# MCU_1726036.net
KiCad netlist of a schematic drawn in Altium Designer
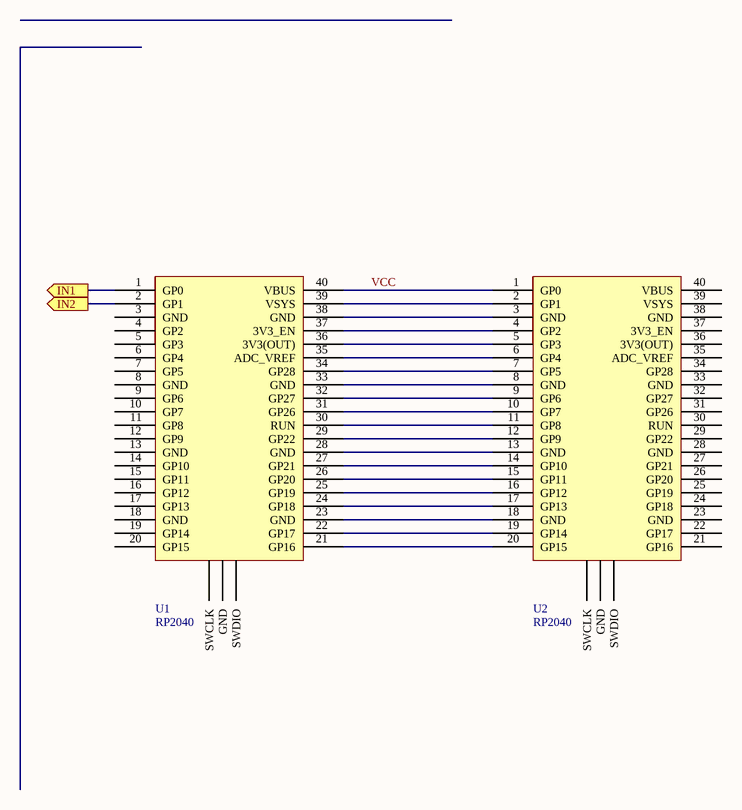
[diagram p0: MCU_1726036.SchDoc]

(export (version "E")
  (design (tool "Eeschema 10.0.6"))
  (components
    (comp (ref "U1") (value "RP2040") (footprint "PICO_MCU") (libsource (lib "PICO_sch") (part "PICO_MCU")))
    (comp (ref "U2") (value "RP2040") (footprint "PICO_MCU") (libsource (lib "PICO_sch") (part "PICO_MCU")))
  )
  (nets
    (net (code "1") (name "/IN1") (class "Default")
      (node (ref "U1") (pin "1") (pinfunction "GP0_1") (pintype "passive"))
    )
    (net (code "2") (name "/IN2") (class "Default")
      (node (ref "U1") (pin "2") (pinfunction "GP1_2") (pintype "passive"))
    )
    (net (code "3") (name "/VCC") (class "Default")
      (node (ref "U1") (pin "40") (pinfunction "VBUS_40") (pintype "passive"))
      (node (ref "U2") (pin "1") (pinfunction "GP0_1") (pintype "passive"))
    )
    (net (code "4") (name "Net-(U1-3V3(OUT))") (class "Default")
      (node (ref "U1") (pin "36") (pinfunction "3V3(OUT)_36") (pintype "passive"))
      (node (ref "U2") (pin "5") (pinfunction "GP3_5") (pintype "passive"))
    )
    (net (code "5") (name "Net-(U1-3V3_EN)") (class "Default")
      (node (ref "U1") (pin "37") (pinfunction "3V3_EN_37") (pintype "passive"))
      (node (ref "U2") (pin "4") (pinfunction "GP2_4") (pintype "passive"))
    )
    (net (code "6") (name "Net-(U1-ADC_VREF)") (class "Default")
      (node (ref "U1") (pin "35") (pinfunction "ADC_VREF_35") (pintype "passive"))
      (node (ref "U2") (pin "6") (pinfunction "GP4_6") (pintype "passive"))
    )
    (net (code "7") (name "Net-(U1-GND-Pad23)") (class "Default")
      (node (ref "U1") (pin "23") (pinfunction "GND_23") (pintype "passive"))
      (node (ref "U2") (pin "18") (pinfunction "GND_18") (pintype "passive"))
    )
    (net (code "8") (name "Net-(U1-GND-Pad28)") (class "Default")
      (node (ref "U1") (pin "28") (pinfunction "GND_28") (pintype "passive"))
      (node (ref "U2") (pin "13") (pinfunction "GND_13") (pintype "passive"))
    )
    (net (code "9") (name "Net-(U1-GND-Pad33)") (class "Default")
      (node (ref "U1") (pin "33") (pinfunction "GND_33") (pintype "passive"))
      (node (ref "U2") (pin "8") (pinfunction "GND_8") (pintype "passive"))
    )
    (net (code "10") (name "Net-(U1-GND-Pad38)") (class "Default")
      (node (ref "U1") (pin "38") (pinfunction "GND_38") (pintype "passive"))
      (node (ref "U2") (pin "3") (pinfunction "GND_3") (pintype "passive"))
    )
    (net (code "11") (name "Net-(U1-GP16)") (class "Default")
      (node (ref "U1") (pin "21") (pinfunction "GP16_21") (pintype "passive"))
      (node (ref "U2") (pin "20") (pinfunction "GP15_20") (pintype "passive"))
    )
    (net (code "12") (name "Net-(U1-GP17)") (class "Default")
      (node (ref "U1") (pin "22") (pinfunction "GP17_22") (pintype "passive"))
      (node (ref "U2") (pin "19") (pinfunction "GP14_19") (pintype "passive"))
    )
    (net (code "13") (name "Net-(U1-GP18)") (class "Default")
      (node (ref "U1") (pin "24") (pinfunction "GP18_24") (pintype "passive"))
      (node (ref "U2") (pin "17") (pinfunction "GP13_17") (pintype "passive"))
    )
    (net (code "14") (name "Net-(U1-GP19)") (class "Default")
      (node (ref "U1") (pin "25") (pinfunction "GP19_25") (pintype "passive"))
      (node (ref "U2") (pin "16") (pinfunction "GP12_16") (pintype "passive"))
    )
    (net (code "15") (name "Net-(U1-GP20)") (class "Default")
      (node (ref "U1") (pin "26") (pinfunction "GP20_26") (pintype "passive"))
      (node (ref "U2") (pin "15") (pinfunction "GP11_15") (pintype "passive"))
    )
    (net (code "16") (name "Net-(U1-GP21)") (class "Default")
      (node (ref "U1") (pin "27") (pinfunction "GP21_27") (pintype "passive"))
      (node (ref "U2") (pin "14") (pinfunction "GP10_14") (pintype "passive"))
    )
    (net (code "17") (name "Net-(U1-GP22)") (class "Default")
      (node (ref "U1") (pin "29") (pinfunction "GP22_29") (pintype "passive"))
      (node (ref "U2") (pin "12") (pinfunction "GP9_12") (pintype "passive"))
    )
    (net (code "18") (name "Net-(U1-GP26)") (class "Default")
      (node (ref "U1") (pin "31") (pinfunction "GP26_31") (pintype "passive"))
      (node (ref "U2") (pin "10") (pinfunction "GP7_10") (pintype "passive"))
    )
    (net (code "19") (name "Net-(U1-GP27)") (class "Default")
      (node (ref "U1") (pin "32") (pinfunction "GP27_32") (pintype "passive"))
      (node (ref "U2") (pin "9") (pinfunction "GP6_9") (pintype "passive"))
    )
    (net (code "20") (name "Net-(U1-GP28)") (class "Default")
      (node (ref "U1") (pin "34") (pinfunction "GP28_34") (pintype "passive"))
      (node (ref "U2") (pin "7") (pinfunction "GP5_7") (pintype "passive"))
    )
    (net (code "21") (name "Net-(U1-RUN)") (class "Default")
      (node (ref "U1") (pin "30") (pinfunction "RUN_30") (pintype "passive"))
      (node (ref "U2") (pin "11") (pinfunction "GP8_11") (pintype "passive"))
    )
    (net (code "22") (name "Net-(U1-VSYS)") (class "Default")
      (node (ref "U1") (pin "39") (pinfunction "VSYS_39") (pintype "passive"))
      (node (ref "U2") (pin "2") (pinfunction "GP1_2") (pintype "passive"))
    )
    (net (code "23") (name "unconnected-(U1-GND-Pad)") (class "Default")
      (node (ref "U1") (pin "") (pinfunction "GND_") (pintype "passive"))
    )
    (net (code "24") (name "unconnected-(U1-GND-Pad3)") (class "Default")
      (node (ref "U1") (pin "3") (pinfunction "GND_3") (pintype "passive"))
    )
    (net (code "25") (name "unconnected-(U1-GND-Pad8)") (class "Default")
      (node (ref "U1") (pin "8") (pinfunction "GND_8") (pintype "passive"))
    )
    (net (code "26") (name "unconnected-(U1-GND-Pad13)") (class "Default")
      (node (ref "U1") (pin "13") (pinfunction "GND_13") (pintype "passive"))
    )
    (net (code "27") (name "unconnected-(U1-GND-Pad18)") (class "Default")
      (node (ref "U1") (pin "18") (pinfunction "GND_18") (pintype "passive"))
    )
    (net (code "28") (name "unconnected-(U1-GP2-Pad4)") (class "Default")
      (node (ref "U1") (pin "4") (pinfunction "GP2_4") (pintype "passive"))
    )
    (net (code "29") (name "unconnected-(U1-GP3-Pad5)") (class "Default")
      (node (ref "U1") (pin "5") (pinfunction "GP3_5") (pintype "passive"))
    )
    (net (code "30") (name "unconnected-(U1-GP4-Pad6)") (class "Default")
      (node (ref "U1") (pin "6") (pinfunction "GP4_6") (pintype "passive"))
    )
    (net (code "31") (name "unconnected-(U1-GP5-Pad7)") (class "Default")
      (node (ref "U1") (pin "7") (pinfunction "GP5_7") (pintype "passive"))
    )
    (net (code "32") (name "unconnected-(U1-GP6-Pad9)") (class "Default")
      (node (ref "U1") (pin "9") (pinfunction "GP6_9") (pintype "passive"))
    )
    (net (code "33") (name "unconnected-(U1-GP7-Pad10)") (class "Default")
      (node (ref "U1") (pin "10") (pinfunction "GP7_10") (pintype "passive"))
    )
    (net (code "34") (name "unconnected-(U1-GP8-Pad11)") (class "Default")
      (node (ref "U1") (pin "11") (pinfunction "GP8_11") (pintype "passive"))
    )
    (net (code "35") (name "unconnected-(U1-GP9-Pad12)") (class "Default")
      (node (ref "U1") (pin "12") (pinfunction "GP9_12") (pintype "passive"))
    )
    (net (code "36") (name "unconnected-(U1-GP10-Pad14)") (class "Default")
      (node (ref "U1") (pin "14") (pinfunction "GP10_14") (pintype "passive"))
    )
    (net (code "37") (name "unconnected-(U1-GP11-Pad15)") (class "Default")
      (node (ref "U1") (pin "15") (pinfunction "GP11_15") (pintype "passive"))
    )
    (net (code "38") (name "unconnected-(U1-GP12-Pad16)") (class "Default")
      (node (ref "U1") (pin "16") (pinfunction "GP12_16") (pintype "passive"))
    )
    (net (code "39") (name "unconnected-(U1-GP13-Pad17)") (class "Default")
      (node (ref "U1") (pin "17") (pinfunction "GP13_17") (pintype "passive"))
    )
    (net (code "40") (name "unconnected-(U1-GP14-Pad19)") (class "Default")
      (node (ref "U1") (pin "19") (pinfunction "GP14_19") (pintype "passive"))
    )
    (net (code "41") (name "unconnected-(U1-GP15-Pad20)") (class "Default")
      (node (ref "U1") (pin "20") (pinfunction "GP15_20") (pintype "passive"))
    )
    (net (code "42") (name "unconnected-(U1-SWCLK-Pad)") (class "Default")
      (node (ref "U1") (pin "") (pinfunction "SWCLK_") (pintype "passive"))
    )
    (net (code "43") (name "unconnected-(U1-SWDIO-Pad)") (class "Default")
      (node (ref "U1") (pin "") (pinfunction "SWDIO_") (pintype "passive"))
    )
    (net (code "44") (name "unconnected-(U2-3V3(OUT)-Pad36)") (class "Default")
      (node (ref "U2") (pin "36") (pinfunction "3V3(OUT)_36") (pintype "passive"))
    )
    (net (code "45") (name "unconnected-(U2-3V3_EN-Pad37)") (class "Default")
      (node (ref "U2") (pin "37") (pinfunction "3V3_EN_37") (pintype "passive"))
    )
    (net (code "46") (name "unconnected-(U2-ADC_VREF-Pad35)") (class "Default")
      (node (ref "U2") (pin "35") (pinfunction "ADC_VREF_35") (pintype "passive"))
    )
    (net (code "47") (name "unconnected-(U2-GND-Pad)") (class "Default")
      (node (ref "U2") (pin "") (pinfunction "GND_") (pintype "passive"))
    )
    (net (code "48") (name "unconnected-(U2-GND-Pad23)") (class "Default")
      (node (ref "U2") (pin "23") (pinfunction "GND_23") (pintype "passive"))
    )
    (net (code "49") (name "unconnected-(U2-GND-Pad28)") (class "Default")
      (node (ref "U2") (pin "28") (pinfunction "GND_28") (pintype "passive"))
    )
    (net (code "50") (name "unconnected-(U2-GND-Pad33)") (class "Default")
      (node (ref "U2") (pin "33") (pinfunction "GND_33") (pintype "passive"))
    )
    (net (code "51") (name "unconnected-(U2-GND-Pad38)") (class "Default")
      (node (ref "U2") (pin "38") (pinfunction "GND_38") (pintype "passive"))
    )
    (net (code "52") (name "unconnected-(U2-GP16-Pad21)") (class "Default")
      (node (ref "U2") (pin "21") (pinfunction "GP16_21") (pintype "passive"))
    )
    (net (code "53") (name "unconnected-(U2-GP17-Pad22)") (class "Default")
      (node (ref "U2") (pin "22") (pinfunction "GP17_22") (pintype "passive"))
    )
    (net (code "54") (name "unconnected-(U2-GP18-Pad24)") (class "Default")
      (node (ref "U2") (pin "24") (pinfunction "GP18_24") (pintype "passive"))
    )
    (net (code "55") (name "unconnected-(U2-GP19-Pad25)") (class "Default")
      (node (ref "U2") (pin "25") (pinfunction "GP19_25") (pintype "passive"))
    )
    (net (code "56") (name "unconnected-(U2-GP20-Pad26)") (class "Default")
      (node (ref "U2") (pin "26") (pinfunction "GP20_26") (pintype "passive"))
    )
    (net (code "57") (name "unconnected-(U2-GP21-Pad27)") (class "Default")
      (node (ref "U2") (pin "27") (pinfunction "GP21_27") (pintype "passive"))
    )
    (net (code "58") (name "unconnected-(U2-GP22-Pad29)") (class "Default")
      (node (ref "U2") (pin "29") (pinfunction "GP22_29") (pintype "passive"))
    )
    (net (code "59") (name "unconnected-(U2-GP26-Pad31)") (class "Default")
      (node (ref "U2") (pin "31") (pinfunction "GP26_31") (pintype "passive"))
    )
    (net (code "60") (name "unconnected-(U2-GP27-Pad32)") (class "Default")
      (node (ref "U2") (pin "32") (pinfunction "GP27_32") (pintype "passive"))
    )
    (net (code "61") (name "unconnected-(U2-GP28-Pad34)") (class "Default")
      (node (ref "U2") (pin "34") (pinfunction "GP28_34") (pintype "passive"))
    )
    (net (code "62") (name "unconnected-(U2-RUN-Pad30)") (class "Default")
      (node (ref "U2") (pin "30") (pinfunction "RUN_30") (pintype "passive"))
    )
    (net (code "63") (name "unconnected-(U2-SWCLK-Pad)") (class "Default")
      (node (ref "U2") (pin "") (pinfunction "SWCLK_") (pintype "passive"))
    )
    (net (code "64") (name "unconnected-(U2-SWDIO-Pad)") (class "Default")
      (node (ref "U2") (pin "") (pinfunction "SWDIO_") (pintype "passive"))
    )
    (net (code "65") (name "unconnected-(U2-VBUS-Pad40)") (class "Default")
      (node (ref "U2") (pin "40") (pinfunction "VBUS_40") (pintype "passive"))
    )
    (net (code "66") (name "unconnected-(U2-VSYS-Pad39)") (class "Default")
      (node (ref "U2") (pin "39") (pinfunction "VSYS_39") (pintype "passive"))
    )
  )
)
